# RGB_Driver.net
KiCad netlist of a schematic drawn in Altium Designer
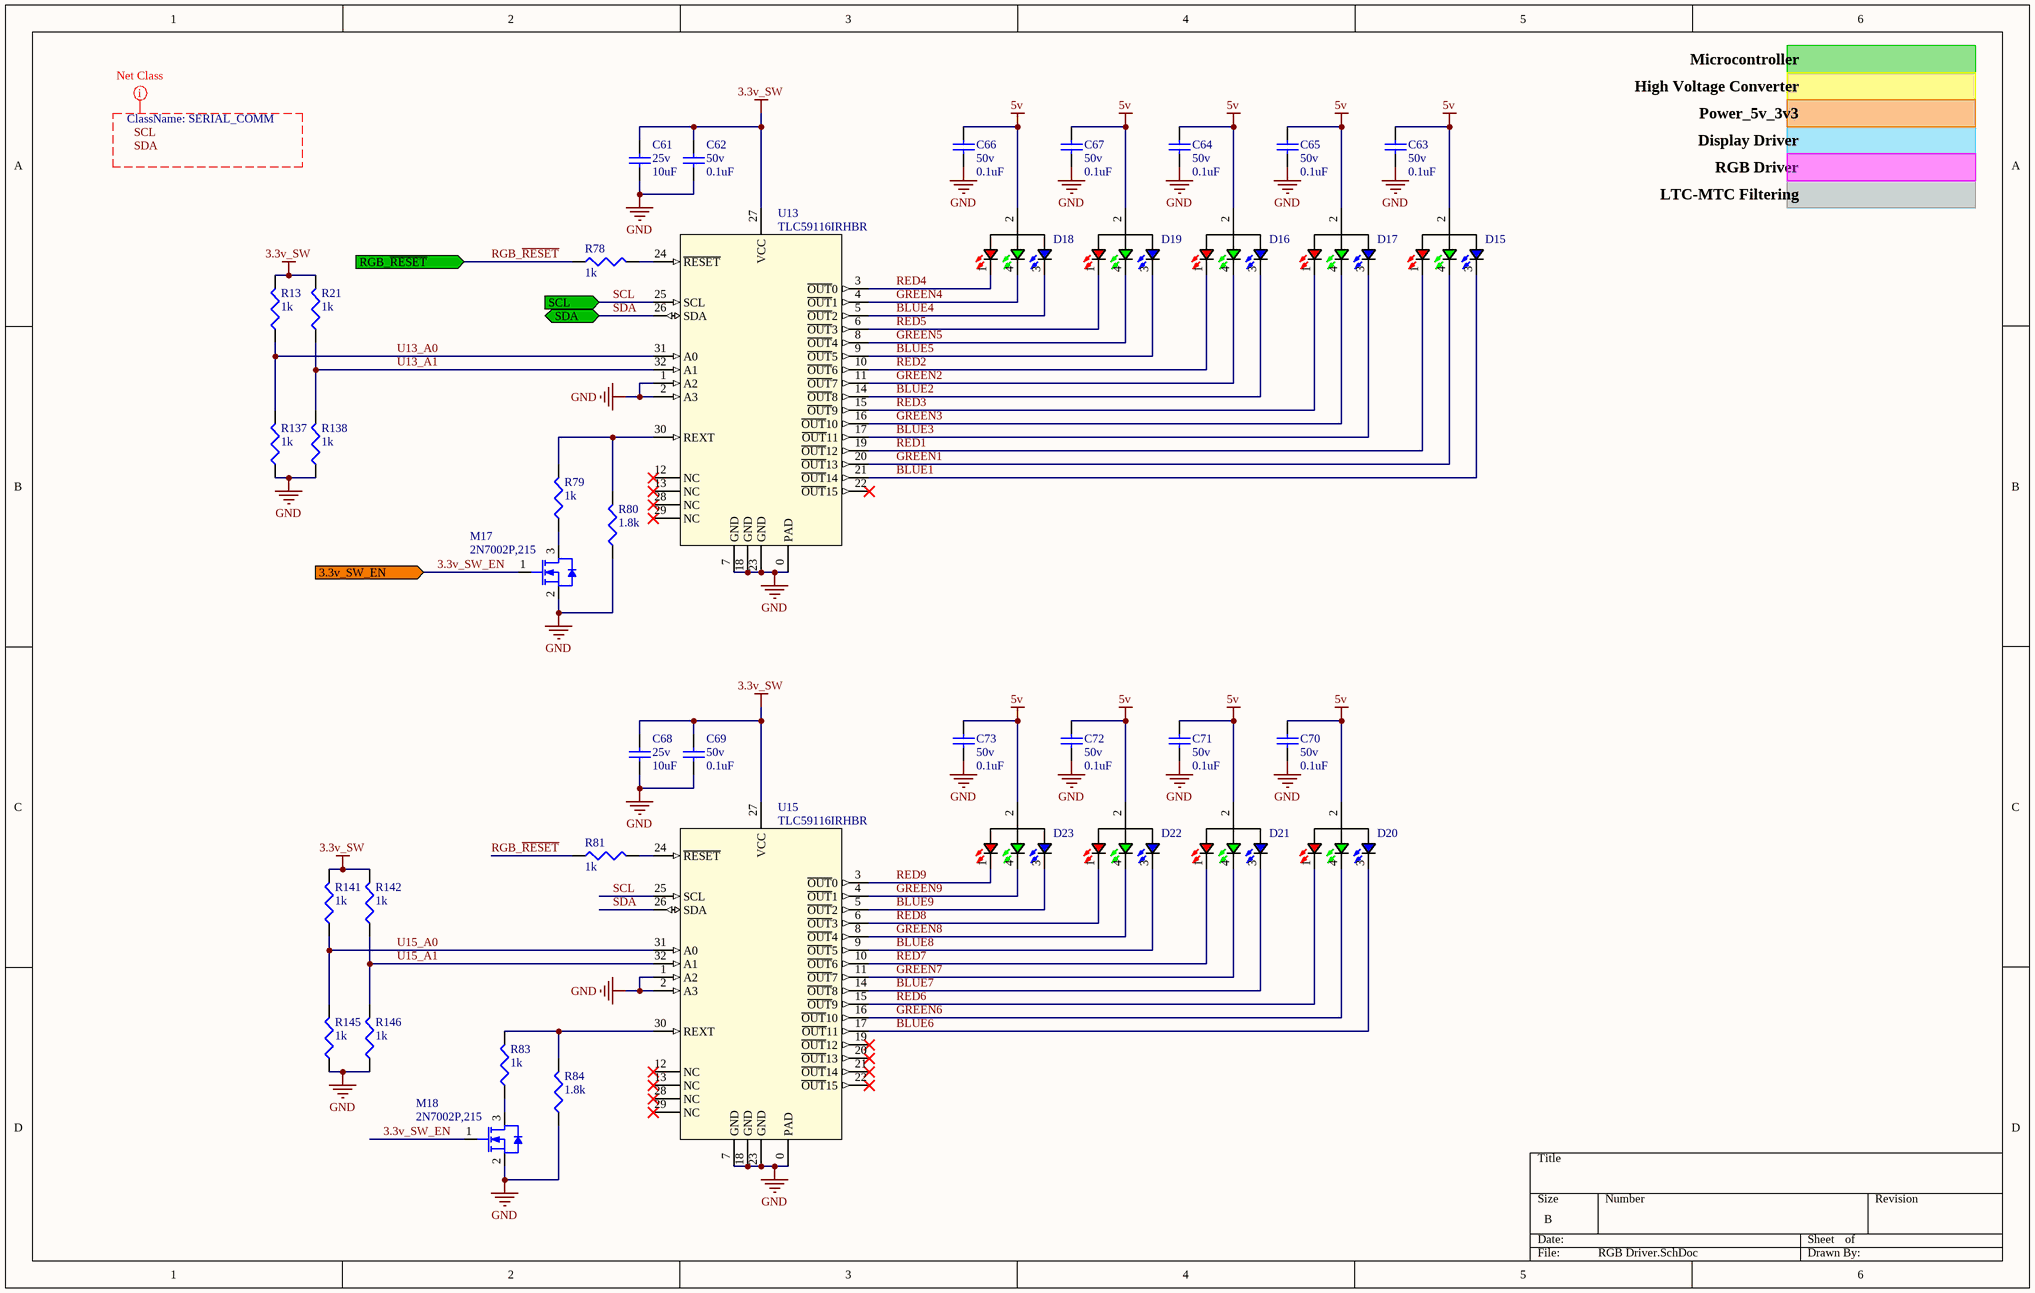
[diagram p0: RGB Driver.SchDoc]

(export (version "E")
  (design (tool "Eeschema 10.0.6"))
  (components
    (comp (ref "C61")
      (value "10uF")
      (footprint "CAP1206R")
      (fields (field (name "TOLERANCE") "10%") (field (name "MFG") "MURATA") (field (name "VOLTAGE") "25v"))
      (libsource (lib "Altium Library") (part "10uF 25v (1206)"))
    )
    (comp (ref "C62")
      (value "0.1uF")
      (footprint "CAP0603R")
      (fields (field (name "MFG") "Vishay") (field (name "VOLTAGE") "50v"))
      (libsource (lib "Altium Library") (part "0.1uF 50v (0603)"))
    )
    (comp (ref "C63")
      (value "0.1uF")
      (footprint "CAP0603R")
      (fields (field (name "MFG") "Vishay") (field (name "VOLTAGE") "50v"))
      (libsource (lib "Altium Library") (part "0.1uF 50v (0603)"))
    )
    (comp (ref "C64")
      (value "0.1uF")
      (footprint "CAP0603R")
      (fields (field (name "MFG") "Vishay") (field (name "VOLTAGE") "50v"))
      (libsource (lib "Altium Library") (part "0.1uF 50v (0603)"))
    )
    (comp (ref "C65")
      (value "0.1uF")
      (footprint "CAP0603R")
      (fields (field (name "MFG") "Vishay") (field (name "VOLTAGE") "50v"))
      (libsource (lib "Altium Library") (part "0.1uF 50v (0603)"))
    )
    (comp (ref "C66")
      (value "0.1uF")
      (footprint "CAP0603R")
      (fields (field (name "MFG") "Vishay") (field (name "VOLTAGE") "50v"))
      (libsource (lib "Altium Library") (part "0.1uF 50v (0603)"))
    )
    (comp (ref "C67")
      (value "0.1uF")
      (footprint "CAP0603R")
      (fields (field (name "MFG") "Vishay") (field (name "VOLTAGE") "50v"))
      (libsource (lib "Altium Library") (part "0.1uF 50v (0603)"))
    )
    (comp (ref "C68")
      (value "10uF")
      (footprint "CAP1206R")
      (fields (field (name "TOLERANCE") "10%") (field (name "MFG") "MURATA") (field (name "VOLTAGE") "25v"))
      (libsource (lib "Altium Library") (part "10uF 25v (1206)"))
    )
    (comp (ref "C69")
      (value "0.1uF")
      (footprint "CAP0603R")
      (fields (field (name "MFG") "Vishay") (field (name "VOLTAGE") "50v"))
      (libsource (lib "Altium Library") (part "0.1uF 50v (0603)"))
    )
    (comp (ref "C70")
      (value "0.1uF")
      (footprint "CAP0603R")
      (fields (field (name "MFG") "Vishay") (field (name "VOLTAGE") "50v"))
      (libsource (lib "Altium Library") (part "0.1uF 50v (0603)"))
    )
    (comp (ref "C71")
      (value "0.1uF")
      (footprint "CAP0603R")
      (fields (field (name "MFG") "Vishay") (field (name "VOLTAGE") "50v"))
      (libsource (lib "Altium Library") (part "0.1uF 50v (0603)"))
    )
    (comp (ref "C72")
      (value "0.1uF")
      (footprint "CAP0603R")
      (fields (field (name "MFG") "Vishay") (field (name "VOLTAGE") "50v"))
      (libsource (lib "Altium Library") (part "0.1uF 50v (0603)"))
    )
    (comp (ref "C73")
      (value "0.1uF")
      (footprint "CAP0603R")
      (fields (field (name "MFG") "Vishay") (field (name "VOLTAGE") "50v"))
      (libsource (lib "Altium Library") (part "0.1uF 50v (0603)"))
    )
    (comp (ref "D15")
      (value "XZMDKCBDDG45S-9")
      (footprint "XZMDKCBDDG45S-9")
      (description "Reverse Gullwing RGB LED")
      (fields (field (name "MFG") "SUN LED"))
      (libsource (lib "Altium Library") (part "XZMDKCBDDG45S-9"))
    )
    (comp (ref "D16")
      (value "XZMDKCBDDG45S-9")
      (footprint "XZMDKCBDDG45S-9")
      (description "Reverse Gullwing RGB LED")
      (fields (field (name "MFG") "SUN LED"))
      (libsource (lib "Altium Library") (part "XZMDKCBDDG45S-9"))
    )
    (comp (ref "D17")
      (value "XZMDKCBDDG45S-9")
      (footprint "XZMDKCBDDG45S-9")
      (description "Reverse Gullwing RGB LED")
      (fields (field (name "MFG") "SUN LED"))
      (libsource (lib "Altium Library") (part "XZMDKCBDDG45S-9"))
    )
    (comp (ref "D18")
      (value "XZMDKCBDDG45S-9")
      (footprint "XZMDKCBDDG45S-9")
      (description "Reverse Gullwing RGB LED")
      (fields (field (name "MFG") "SUN LED"))
      (libsource (lib "Altium Library") (part "XZMDKCBDDG45S-9"))
    )
    (comp (ref "D19")
      (value "XZMDKCBDDG45S-9")
      (footprint "XZMDKCBDDG45S-9")
      (description "Reverse Gullwing RGB LED")
      (fields (field (name "MFG") "SUN LED"))
      (libsource (lib "Altium Library") (part "XZMDKCBDDG45S-9"))
    )
    (comp (ref "D20")
      (value "XZMDKCBDDG45S-9")
      (footprint "XZMDKCBDDG45S-9")
      (description "Reverse Gullwing RGB LED")
      (fields (field (name "MFG") "SUN LED"))
      (libsource (lib "Altium Library") (part "XZMDKCBDDG45S-9"))
    )
    (comp (ref "D21")
      (value "XZMDKCBDDG45S-9")
      (footprint "XZMDKCBDDG45S-9")
      (description "Reverse Gullwing RGB LED")
      (fields (field (name "MFG") "SUN LED"))
      (libsource (lib "Altium Library") (part "XZMDKCBDDG45S-9"))
    )
    (comp (ref "D22")
      (value "XZMDKCBDDG45S-9")
      (footprint "XZMDKCBDDG45S-9")
      (description "Reverse Gullwing RGB LED")
      (fields (field (name "MFG") "SUN LED"))
      (libsource (lib "Altium Library") (part "XZMDKCBDDG45S-9"))
    )
    (comp (ref "D23")
      (value "XZMDKCBDDG45S-9")
      (footprint "XZMDKCBDDG45S-9")
      (description "Reverse Gullwing RGB LED")
      (fields (field (name "MFG") "SUN LED"))
      (libsource (lib "Altium Library") (part "XZMDKCBDDG45S-9"))
    )
    (comp (ref "M17")
      (value "2N7002P,215")
      (footprint "SOT23-3M")
      (description "NFET_SINGLE_360mA_60V")
      (fields (field (name "MFG") "NXP"))
      (libsource (lib "Altium Library") (part "2N7002"))
    )
    (comp (ref "M18")
      (value "2N7002P,215")
      (footprint "SOT23-3M")
      (description "NFET_SINGLE_360mA_60V")
      (fields (field (name "MFG") "NXP"))
      (libsource (lib "Altium Library") (part "2N7002"))
    )
    (comp (ref "R13")
      (value "1k")
      (footprint "RES0402R")
      (fields (field (name "TOLERANCE") "1%") (field (name "POWER") "63mW") (field (name "MFG") "Vishay"))
      (libsource (lib "Altium Library") (part "1k (0402)"))
    )
    (comp (ref "R21")
      (value "1k")
      (footprint "RES0402R")
      (fields (field (name "TOLERANCE") "1%") (field (name "POWER") "63mW") (field (name "MFG") "Vishay"))
      (libsource (lib "Altium Library") (part "1k (0402)"))
    )
    (comp (ref "R78")
      (value "1k")
      (footprint "RES0402R")
      (fields (field (name "TOLERANCE") "1%") (field (name "POWER") "63mW") (field (name "MFG") "Vishay"))
      (libsource (lib "Altium Library") (part "1k (0402)"))
    )
    (comp (ref "R79")
      (value "1k")
      (footprint "RES0402R")
      (fields (field (name "TOLERANCE") "1%") (field (name "POWER") "63mW") (field (name "MFG") "Vishay"))
      (libsource (lib "Altium Library") (part "1k (0402)"))
    )
    (comp (ref "R80")
      (value "1.8k")
      (footprint "RES0402R")
      (fields (field (name "TOLERANCE") "1%") (field (name "POWER") "63mW") (field (name "MFG") "Vishay"))
      (libsource (lib "Altium Library") (part "1.8k (0402)"))
    )
    (comp (ref "R81")
      (value "1k")
      (footprint "RES0402R")
      (fields (field (name "TOLERANCE") "1%") (field (name "POWER") "63mW") (field (name "MFG") "Vishay"))
      (libsource (lib "Altium Library") (part "1k (0402)"))
    )
    (comp (ref "R83")
      (value "1k")
      (footprint "RES0402R")
      (fields (field (name "TOLERANCE") "1%") (field (name "POWER") "63mW") (field (name "MFG") "Vishay"))
      (libsource (lib "Altium Library") (part "1k (0402)"))
    )
    (comp (ref "R84")
      (value "1.8k")
      (footprint "RES0402R")
      (fields (field (name "TOLERANCE") "1%") (field (name "POWER") "63mW") (field (name "MFG") "Vishay"))
      (libsource (lib "Altium Library") (part "1.8k (0402)"))
    )
    (comp (ref "R137")
      (value "1k")
      (footprint "RES0402R")
      (fields (field (name "TOLERANCE") "1%") (field (name "POWER") "63mW") (field (name "MFG") "Vishay"))
      (libsource (lib "Altium Library") (part "1k (0402)"))
    )
    (comp (ref "R138")
      (value "1k")
      (footprint "RES0402R")
      (fields (field (name "TOLERANCE") "1%") (field (name "POWER") "63mW") (field (name "MFG") "Vishay"))
      (libsource (lib "Altium Library") (part "1k (0402)"))
    )
    (comp (ref "R141")
      (value "1k")
      (footprint "RES0402R")
      (fields (field (name "TOLERANCE") "1%") (field (name "POWER") "63mW") (field (name "MFG") "Vishay"))
      (libsource (lib "Altium Library") (part "1k (0402)"))
    )
    (comp (ref "R142")
      (value "1k")
      (footprint "RES0402R")
      (fields (field (name "TOLERANCE") "1%") (field (name "POWER") "63mW") (field (name "MFG") "Vishay"))
      (libsource (lib "Altium Library") (part "1k (0402)"))
    )
    (comp (ref "R145")
      (value "1k")
      (footprint "RES0402R")
      (fields (field (name "TOLERANCE") "1%") (field (name "POWER") "63mW") (field (name "MFG") "Vishay"))
      (libsource (lib "Altium Library") (part "1k (0402)"))
    )
    (comp (ref "R146")
      (value "1k")
      (footprint "RES0402R")
      (fields (field (name "TOLERANCE") "1%") (field (name "POWER") "63mW") (field (name "MFG") "Vishay"))
      (libsource (lib "Altium Library") (part "1k (0402)"))
    )
    (comp (ref "U13")
      (value "TLC59116IRHBR")
      (footprint "QFN32")
      (description "LED Driver, 16ch, Individual dimming")
      (fields (field (name "MFG") "TI"))
      (libsource (lib "Altium Library") (part "TLC59116IRHBR"))
    )
    (comp (ref "U15")
      (value "TLC59116IRHBR")
      (footprint "QFN32")
      (description "LED Driver, 16ch, Individual dimming")
      (fields (field (name "MFG") "TI"))
      (libsource (lib "Altium Library") (part "TLC59116IRHBR"))
    )
  )
  (nets
    (net (code "1") (name "/3.3v_SW_EN") (class "Default")
      (node (ref "M17") (pin "1") (pinfunction "GATE_1") (pintype "passive"))
      (node (ref "M18") (pin "1") (pinfunction "GATE_1") (pintype "passive"))
    )
    (net (code "2") (name "/BLUE1") (class "Default")
      (node (ref "D15") (pin "3") (pinfunction "B_3") (pintype "passive"))
      (node (ref "U13") (pin "21") (pinfunction "~{OUT}14_21") (pintype "output"))
    )
    (net (code "3") (name "/BLUE2") (class "Default")
      (node (ref "D16") (pin "3") (pinfunction "B_3") (pintype "passive"))
      (node (ref "U13") (pin "14") (pinfunction "~{OUT}8_14") (pintype "output"))
    )
    (net (code "4") (name "/BLUE3") (class "Default")
      (node (ref "D17") (pin "3") (pinfunction "B_3") (pintype "passive"))
      (node (ref "U13") (pin "17") (pinfunction "~{OUT}11_17") (pintype "output"))
    )
    (net (code "5") (name "/BLUE4") (class "Default")
      (node (ref "D18") (pin "3") (pinfunction "B_3") (pintype "passive"))
      (node (ref "U13") (pin "5") (pinfunction "~{OUT}2_5") (pintype "output"))
    )
    (net (code "6") (name "/BLUE5") (class "Default")
      (node (ref "D19") (pin "3") (pinfunction "B_3") (pintype "passive"))
      (node (ref "U13") (pin "9") (pinfunction "~{OUT}5_9") (pintype "output"))
    )
    (net (code "7") (name "/BLUE6") (class "Default")
      (node (ref "D20") (pin "3") (pinfunction "B_3") (pintype "passive"))
      (node (ref "U15") (pin "17") (pinfunction "~{OUT}11_17") (pintype "output"))
    )
    (net (code "8") (name "/BLUE7") (class "Default")
      (node (ref "D21") (pin "3") (pinfunction "B_3") (pintype "passive"))
      (node (ref "U15") (pin "14") (pinfunction "~{OUT}8_14") (pintype "output"))
    )
    (net (code "9") (name "/BLUE8") (class "Default")
      (node (ref "D22") (pin "3") (pinfunction "B_3") (pintype "passive"))
      (node (ref "U15") (pin "9") (pinfunction "~{OUT}5_9") (pintype "output"))
    )
    (net (code "10") (name "/BLUE9") (class "Default")
      (node (ref "D23") (pin "3") (pinfunction "B_3") (pintype "passive"))
      (node (ref "U15") (pin "5") (pinfunction "~{OUT}2_5") (pintype "output"))
    )
    (net (code "11") (name "/GREEN1") (class "Default")
      (node (ref "D15") (pin "4") (pinfunction "G_4") (pintype "passive"))
      (node (ref "U13") (pin "20") (pinfunction "~{OUT}13_20") (pintype "output"))
    )
    (net (code "12") (name "/GREEN2") (class "Default")
      (node (ref "D16") (pin "4") (pinfunction "G_4") (pintype "passive"))
      (node (ref "U13") (pin "11") (pinfunction "~{OUT}7_11") (pintype "output"))
    )
    (net (code "13") (name "/GREEN3") (class "Default")
      (node (ref "D17") (pin "4") (pinfunction "G_4") (pintype "passive"))
      (node (ref "U13") (pin "16") (pinfunction "~{OUT}10_16") (pintype "output"))
    )
    (net (code "14") (name "/GREEN4") (class "Default")
      (node (ref "D18") (pin "4") (pinfunction "G_4") (pintype "passive"))
      (node (ref "U13") (pin "4") (pinfunction "~{OUT}1_4") (pintype "output"))
    )
    (net (code "15") (name "/GREEN5") (class "Default")
      (node (ref "D19") (pin "4") (pinfunction "G_4") (pintype "passive"))
      (node (ref "U13") (pin "8") (pinfunction "~{OUT}4_8") (pintype "output"))
    )
    (net (code "16") (name "/GREEN6") (class "Default")
      (node (ref "D20") (pin "4") (pinfunction "G_4") (pintype "passive"))
      (node (ref "U15") (pin "16") (pinfunction "~{OUT}10_16") (pintype "output"))
    )
    (net (code "17") (name "/GREEN7") (class "Default")
      (node (ref "D21") (pin "4") (pinfunction "G_4") (pintype "passive"))
      (node (ref "U15") (pin "11") (pinfunction "~{OUT}7_11") (pintype "output"))
    )
    (net (code "18") (name "/GREEN8") (class "Default")
      (node (ref "D22") (pin "4") (pinfunction "G_4") (pintype "passive"))
      (node (ref "U15") (pin "8") (pinfunction "~{OUT}4_8") (pintype "output"))
    )
    (net (code "19") (name "/GREEN9") (class "Default")
      (node (ref "D23") (pin "4") (pinfunction "G_4") (pintype "passive"))
      (node (ref "U15") (pin "4") (pinfunction "~{OUT}1_4") (pintype "output"))
    )
    (net (code "20") (name "/RED1") (class "Default")
      (node (ref "D15") (pin "1") (pinfunction "R_1") (pintype "passive"))
      (node (ref "U13") (pin "19") (pinfunction "~{OUT}12_19") (pintype "output"))
    )
    (net (code "21") (name "/RED2") (class "Default")
      (node (ref "D16") (pin "1") (pinfunction "R_1") (pintype "passive"))
      (node (ref "U13") (pin "10") (pinfunction "~{OUT}6_10") (pintype "output"))
    )
    (net (code "22") (name "/RED3") (class "Default")
      (node (ref "D17") (pin "1") (pinfunction "R_1") (pintype "passive"))
      (node (ref "U13") (pin "15") (pinfunction "~{OUT}9_15") (pintype "output"))
    )
    (net (code "23") (name "/RED4") (class "Default")
      (node (ref "D18") (pin "1") (pinfunction "R_1") (pintype "passive"))
      (node (ref "U13") (pin "3") (pinfunction "~{OUT}0_3") (pintype "output"))
    )
    (net (code "24") (name "/RED5") (class "Default")
      (node (ref "D19") (pin "1") (pinfunction "R_1") (pintype "passive"))
      (node (ref "U13") (pin "6") (pinfunction "~{OUT}3_6") (pintype "output"))
    )
    (net (code "25") (name "/RED6") (class "Default")
      (node (ref "D20") (pin "1") (pinfunction "R_1") (pintype "passive"))
      (node (ref "U15") (pin "15") (pinfunction "~{OUT}9_15") (pintype "output"))
    )
    (net (code "26") (name "/RED7") (class "Default")
      (node (ref "D21") (pin "1") (pinfunction "R_1") (pintype "passive"))
      (node (ref "U15") (pin "10") (pinfunction "~{OUT}6_10") (pintype "output"))
    )
    (net (code "27") (name "/RED8") (class "Default")
      (node (ref "D22") (pin "1") (pinfunction "R_1") (pintype "passive"))
      (node (ref "U15") (pin "6") (pinfunction "~{OUT}3_6") (pintype "output"))
    )
    (net (code "28") (name "/RED9") (class "Default")
      (node (ref "D23") (pin "1") (pinfunction "R_1") (pintype "passive"))
      (node (ref "U15") (pin "3") (pinfunction "~{OUT}0_3") (pintype "output"))
    )
    (net (code "29") (name "/RGB_~{RESET}") (class "Default")
      (node (ref "R78") (pin "1") (pinfunction "1_1") (pintype "passive"))
      (node (ref "R81") (pin "1") (pinfunction "1_1") (pintype "passive"))
    )
    (net (code "30") (name "/SCL") (class "Default")
      (node (ref "U13") (pin "25") (pinfunction "SCL_25") (pintype "input"))
      (node (ref "U15") (pin "25") (pinfunction "SCL_25") (pintype "input"))
    )
    (net (code "31") (name "/SDA") (class "Default")
      (node (ref "U13") (pin "26") (pinfunction "SDA_26") (pintype "bidirectional"))
      (node (ref "U15") (pin "26") (pinfunction "SDA_26") (pintype "bidirectional"))
    )
    (net (code "32") (name "/U13_A0") (class "Default")
      (node (ref "R13") (pin "1") (pinfunction "1_1") (pintype "passive"))
      (node (ref "R137") (pin "2") (pinfunction "2_2") (pintype "passive"))
      (node (ref "U13") (pin "31") (pinfunction "A0_31") (pintype "input"))
    )
    (net (code "33") (name "/U13_A1") (class "Default")
      (node (ref "R138") (pin "2") (pinfunction "2_2") (pintype "passive"))
      (node (ref "R21") (pin "1") (pinfunction "1_1") (pintype "passive"))
      (node (ref "U13") (pin "32") (pinfunction "A1_32") (pintype "input"))
    )
    (net (code "34") (name "/U15_A0") (class "Default")
      (node (ref "R141") (pin "1") (pinfunction "1_1") (pintype "passive"))
      (node (ref "R145") (pin "2") (pinfunction "2_2") (pintype "passive"))
      (node (ref "U15") (pin "31") (pinfunction "A0_31") (pintype "input"))
    )
    (net (code "35") (name "/U15_A1") (class "Default")
      (node (ref "R142") (pin "1") (pinfunction "1_1") (pintype "passive"))
      (node (ref "R146") (pin "2") (pinfunction "2_2") (pintype "passive"))
      (node (ref "U15") (pin "32") (pinfunction "A1_32") (pintype "input"))
    )
    (net (code "36") (name "3.3v_SW") (class "Default")
      (node (ref "C61") (pin "1") (pinfunction "1_1") (pintype "passive"))
      (node (ref "C62") (pin "2") (pinfunction "2_2") (pintype "passive"))
      (node (ref "C68") (pin "1") (pinfunction "1_1") (pintype "passive"))
      (node (ref "C69") (pin "2") (pinfunction "2_2") (pintype "passive"))
      (node (ref "R13") (pin "2") (pinfunction "2_2") (pintype "passive"))
      (node (ref "R141") (pin "2") (pinfunction "2_2") (pintype "passive"))
      (node (ref "R142") (pin "2") (pinfunction "2_2") (pintype "passive"))
      (node (ref "R21") (pin "2") (pinfunction "2_2") (pintype "passive"))
      (node (ref "U13") (pin "27") (pinfunction "VCC_27") (pintype "power_in"))
      (node (ref "U15") (pin "27") (pinfunction "VCC_27") (pintype "power_in"))
    )
    (net (code "37") (name "5v") (class "Default")
      (node (ref "C63") (pin "1") (pinfunction "1_1") (pintype "passive"))
      (node (ref "C64") (pin "1") (pinfunction "1_1") (pintype "passive"))
      (node (ref "C65") (pin "1") (pinfunction "1_1") (pintype "passive"))
      (node (ref "C66") (pin "1") (pinfunction "1_1") (pintype "passive"))
      (node (ref "C67") (pin "1") (pinfunction "1_1") (pintype "passive"))
      (node (ref "C70") (pin "1") (pinfunction "1_1") (pintype "passive"))
      (node (ref "C71") (pin "1") (pinfunction "1_1") (pintype "passive"))
      (node (ref "C72") (pin "1") (pinfunction "1_1") (pintype "passive"))
      (node (ref "C73") (pin "1") (pinfunction "1_1") (pintype "passive"))
      (node (ref "D15") (pin "2") (pinfunction "COMMON_2") (pintype "passive"))
      (node (ref "D16") (pin "2") (pinfunction "COMMON_2") (pintype "passive"))
      (node (ref "D17") (pin "2") (pinfunction "COMMON_2") (pintype "passive"))
      (node (ref "D18") (pin "2") (pinfunction "COMMON_2") (pintype "passive"))
      (node (ref "D19") (pin "2") (pinfunction "COMMON_2") (pintype "passive"))
      (node (ref "D20") (pin "2") (pinfunction "COMMON_2") (pintype "passive"))
      (node (ref "D21") (pin "2") (pinfunction "COMMON_2") (pintype "passive"))
      (node (ref "D22") (pin "2") (pinfunction "COMMON_2") (pintype "passive"))
      (node (ref "D23") (pin "2") (pinfunction "COMMON_2") (pintype "passive"))
    )
    (net (code "38") (name "GND") (class "Default")
      (node (ref "C61") (pin "2") (pinfunction "2_2") (pintype "passive"))
      (node (ref "C62") (pin "1") (pinfunction "1_1") (pintype "passive"))
      (node (ref "C63") (pin "2") (pinfunction "2_2") (pintype "passive"))
      (node (ref "C64") (pin "2") (pinfunction "2_2") (pintype "passive"))
      (node (ref "C65") (pin "2") (pinfunction "2_2") (pintype "passive"))
      (node (ref "C66") (pin "2") (pinfunction "2_2") (pintype "passive"))
      (node (ref "C67") (pin "2") (pinfunction "2_2") (pintype "passive"))
      (node (ref "C68") (pin "2") (pinfunction "2_2") (pintype "passive"))
      (node (ref "C69") (pin "1") (pinfunction "1_1") (pintype "passive"))
      (node (ref "C70") (pin "2") (pinfunction "2_2") (pintype "passive"))
      (node (ref "C71") (pin "2") (pinfunction "2_2") (pintype "passive"))
      (node (ref "C72") (pin "2") (pinfunction "2_2") (pintype "passive"))
      (node (ref "C73") (pin "2") (pinfunction "2_2") (pintype "passive"))
      (node (ref "M17") (pin "2") (pinfunction "SOURCE_2") (pintype "passive"))
      (node (ref "M18") (pin "2") (pinfunction "SOURCE_2") (pintype "passive"))
      (node (ref "R137") (pin "1") (pinfunction "1_1") (pintype "passive"))
      (node (ref "R138") (pin "1") (pinfunction "1_1") (pintype "passive"))
      (node (ref "R145") (pin "1") (pinfunction "1_1") (pintype "passive"))
      (node (ref "R146") (pin "1") (pinfunction "1_1") (pintype "passive"))
      (node (ref "R80") (pin "1") (pinfunction "1_1") (pintype "passive"))
      (node (ref "R84") (pin "1") (pinfunction "1_1") (pintype "passive"))
      (node (ref "U13") (pin "0") (pinfunction "PAD_0") (pintype "power_in"))
      (node (ref "U13") (pin "1") (pinfunction "A2_1") (pintype "input"))
      (node (ref "U13") (pin "18") (pinfunction "GND_18") (pintype "power_in"))
      (node (ref "U13") (pin "2") (pinfunction "A3_2") (pintype "input"))
      (node (ref "U13") (pin "23") (pinfunction "GND_23") (pintype "power_in"))
      (node (ref "U13") (pin "7") (pinfunction "GND_7") (pintype "power_in"))
      (node (ref "U15") (pin "0") (pinfunction "PAD_0") (pintype "power_in"))
      (node (ref "U15") (pin "1") (pinfunction "A2_1") (pintype "input"))
      (node (ref "U15") (pin "18") (pinfunction "GND_18") (pintype "power_in"))
      (node (ref "U15") (pin "2") (pinfunction "A3_2") (pintype "input"))
      (node (ref "U15") (pin "23") (pinfunction "GND_23") (pintype "power_in"))
      (node (ref "U15") (pin "7") (pinfunction "GND_7") (pintype "power_in"))
    )
    (net (code "39") (name "Net-(M17-DRAIN)") (class "Default")
      (node (ref "M17") (pin "3") (pinfunction "DRAIN_3") (pintype "passive"))
      (node (ref "R79") (pin "1") (pinfunction "1_1") (pintype "passive"))
    )
    (net (code "40") (name "Net-(M18-DRAIN)") (class "Default")
      (node (ref "M18") (pin "3") (pinfunction "DRAIN_3") (pintype "passive"))
      (node (ref "R83") (pin "1") (pinfunction "1_1") (pintype "passive"))
    )
    (net (code "41") (name "Net-(U13-REXT)") (class "Default")
      (node (ref "R79") (pin "2") (pinfunction "2_2") (pintype "passive"))
      (node (ref "R80") (pin "2") (pinfunction "2_2") (pintype "passive"))
      (node (ref "U13") (pin "30") (pinfunction "REXT_30") (pintype "input"))
    )
    (net (code "42") (name "Net-(U13-~{RESET})") (class "Default")
      (node (ref "R78") (pin "2") (pinfunction "2_2") (pintype "passive"))
      (node (ref "U13") (pin "24") (pinfunction "~{RESET}_24") (pintype "input"))
    )
    (net (code "43") (name "Net-(U15-REXT)") (class "Default")
      (node (ref "R83") (pin "2") (pinfunction "2_2") (pintype "passive"))
      (node (ref "R84") (pin "2") (pinfunction "2_2") (pintype "passive"))
      (node (ref "U15") (pin "30") (pinfunction "REXT_30") (pintype "input"))
    )
    (net (code "44") (name "Net-(U15-~{RESET})") (class "Default")
      (node (ref "R81") (pin "2") (pinfunction "2_2") (pintype "passive"))
      (node (ref "U15") (pin "24") (pinfunction "~{RESET}_24") (pintype "input"))
    )
    (net (code "45") (name "unconnected-(U13-NC-Pad12)") (class "Default")
      (node (ref "U13") (pin "12") (pinfunction "NC_12") (pintype "passive+no_connect"))
    )
    (net (code "46") (name "unconnected-(U13-NC-Pad13)") (class "Default")
      (node (ref "U13") (pin "13") (pinfunction "NC_13") (pintype "passive+no_connect"))
    )
    (net (code "47") (name "unconnected-(U13-NC-Pad28)") (class "Default")
      (node (ref "U13") (pin "28") (pinfunction "NC_28") (pintype "passive+no_connect"))
    )
    (net (code "48") (name "unconnected-(U13-NC-Pad29)") (class "Default")
      (node (ref "U13") (pin "29") (pinfunction "NC_29") (pintype "passive+no_connect"))
    )
    (net (code "49") (name "unconnected-(U13-~{OUT}15-Pad22)") (class "Default")
      (node (ref "U13") (pin "22") (pinfunction "~{OUT}15_22") (pintype "output+no_connect"))
    )
    (net (code "50") (name "unconnected-(U15-NC-Pad12)") (class "Default")
      (node (ref "U15") (pin "12") (pinfunction "NC_12") (pintype "passive+no_connect"))
    )
    (net (code "51") (name "unconnected-(U15-NC-Pad13)") (class "Default")
      (node (ref "U15") (pin "13") (pinfunction "NC_13") (pintype "passive+no_connect"))
    )
    (net (code "52") (name "unconnected-(U15-NC-Pad28)") (class "Default")
      (node (ref "U15") (pin "28") (pinfunction "NC_28") (pintype "passive+no_connect"))
    )
    (net (code "53") (name "unconnected-(U15-NC-Pad29)") (class "Default")
      (node (ref "U15") (pin "29") (pinfunction "NC_29") (pintype "passive+no_connect"))
    )
    (net (code "54") (name "unconnected-(U15-~{OUT}12-Pad19)") (class "Default")
      (node (ref "U15") (pin "19") (pinfunction "~{OUT}12_19") (pintype "output+no_connect"))
    )
    (net (code "55") (name "unconnected-(U15-~{OUT}13-Pad20)") (class "Default")
      (node (ref "U15") (pin "20") (pinfunction "~{OUT}13_20") (pintype "output+no_connect"))
    )
    (net (code "56") (name "unconnected-(U15-~{OUT}14-Pad21)") (class "Default")
      (node (ref "U15") (pin "21") (pinfunction "~{OUT}14_21") (pintype "output+no_connect"))
    )
    (net (code "57") (name "unconnected-(U15-~{OUT}15-Pad22)") (class "Default")
      (node (ref "U15") (pin "22") (pinfunction "~{OUT}15_22") (pintype "output+no_connect"))
    )
  )
)
